# Gumstix_Overo.net
KiCad netlist of a schematic drawn in Altium Designer
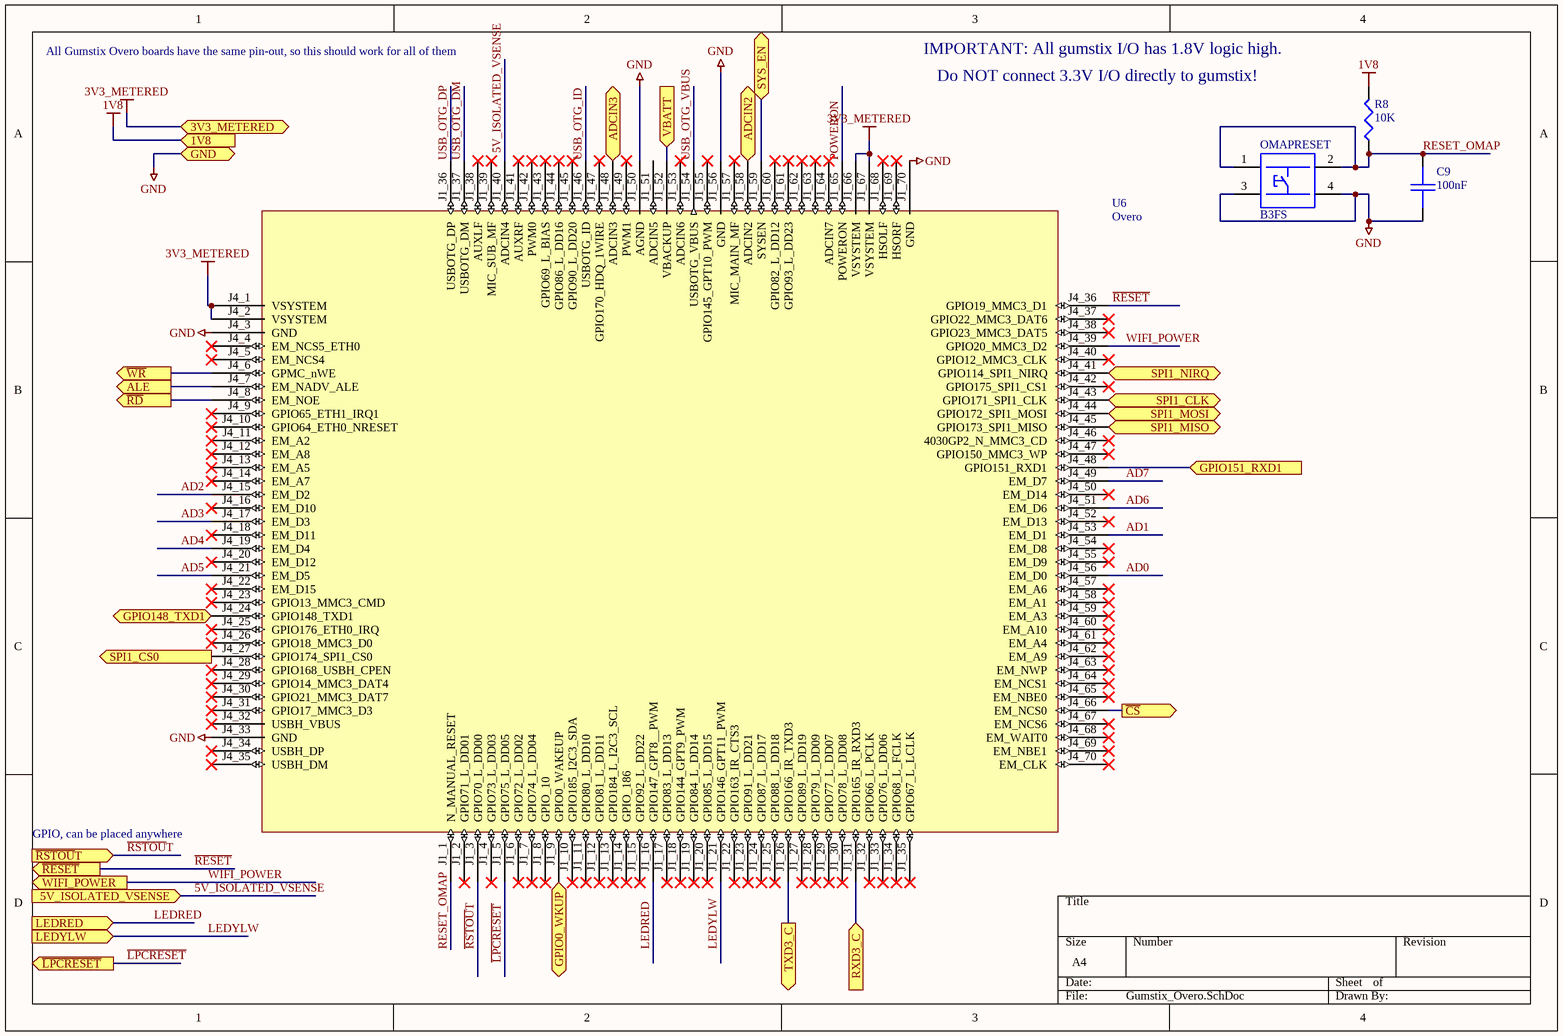
[diagram p0: Gumstix_Overo.SchDoc]

(export (version "E")
  (design (tool "Eeschema 10.0.6"))
  (components
    (comp (ref "C9")
      (value "100nF")
      (footprint "0603")
      (description "Capacitor")
      (libsource (lib "RCLDQ") (part "CAP"))
    )
    (comp (ref "OMAPRESET")
      (value "B3FS")
      (footprint "B3FS-1052")
      (description "SMD tactile switch")
      (libsource (lib "Miscellaneous") (part "B3FS"))
    )
    (comp (ref "R8")
      (value "10K")
      (footprint "0603")
      (description "Resistor")
      (libsource (lib "RCLDQ") (part "RES1"))
    )
    (comp (ref "U6")
      (value "Overo")
      (footprint "Overo-bare")
      (description "Gumstix Overo Motherboard")
      (libsource (lib "gumstix") (part "Overo"))
    )
  )
  (nets
    (net (code "1") (name "/5V_ISOLATED_VSENSE") (class "Default")
      (node (ref "U6") (pin "J1_40") (pinfunction "ADCIN4_J1_40") (pintype "bidirectional"))
    )
    (net (code "2") (name "/AD0") (class "Default")
      (node (ref "U6") (pin "J4_56") (pinfunction "EM_D0_J4_56") (pintype "bidirectional"))
    )
    (net (code "3") (name "/AD1") (class "Default")
      (node (ref "U6") (pin "J4_53") (pinfunction "EM_D1_J4_53") (pintype "bidirectional"))
    )
    (net (code "4") (name "/AD2") (class "Default")
      (node (ref "U6") (pin "J4_15") (pinfunction "EM_D2_J4_15") (pintype "bidirectional"))
    )
    (net (code "5") (name "/AD3") (class "Default")
      (node (ref "U6") (pin "J4_17") (pinfunction "EM_D3_J4_17") (pintype "bidirectional"))
    )
    (net (code "6") (name "/AD4") (class "Default")
      (node (ref "U6") (pin "J4_19") (pinfunction "EM_D4_J4_19") (pintype "bidirectional"))
    )
    (net (code "7") (name "/AD5") (class "Default")
      (node (ref "U6") (pin "J4_21") (pinfunction "EM_D5_J4_21") (pintype "bidirectional"))
    )
    (net (code "8") (name "/AD6") (class "Default")
      (node (ref "U6") (pin "J4_51") (pinfunction "EM_D6_J4_51") (pintype "bidirectional"))
    )
    (net (code "9") (name "/AD7") (class "Default")
      (node (ref "U6") (pin "J4_49") (pinfunction "EM_D7_J4_49") (pintype "bidirectional"))
    )
    (net (code "10") (name "/ADCIN2") (class "Default")
      (node (ref "U6") (pin "J1_58") (pinfunction "ADCIN2_J1_58") (pintype "bidirectional"))
    )
    (net (code "11") (name "/ADCIN3") (class "Default")
      (node (ref "U6") (pin "J1_48") (pinfunction "ADCIN3_J1_48") (pintype "bidirectional"))
    )
    (net (code "12") (name "/ALE") (class "Default")
      (node (ref "U6") (pin "J4_7") (pinfunction "EM_NADV_ALE_J4_7") (pintype "bidirectional"))
    )
    (net (code "13") (name "/GPIO0_WKUP") (class "Default")
      (node (ref "U6") (pin "J1_9") (pinfunction "GPIO0_WAKEUP_J1_9") (pintype "bidirectional"))
    )
    (net (code "14") (name "/GPIO148_TXD1") (class "Default")
      (node (ref "U6") (pin "J4_24") (pinfunction "GPIO148_TXD1_J4_24") (pintype "bidirectional"))
    )
    (net (code "15") (name "/GPIO151_RXD1") (class "Default")
      (node (ref "U6") (pin "J4_48") (pinfunction "GPIO151_RXD1_J4_48") (pintype "bidirectional"))
    )
    (net (code "16") (name "/LEDRED") (class "Default")
      (node (ref "U6") (pin "J1_16") (pinfunction "GPIO147_GPT8__PWM_J1_16") (pintype "bidirectional"))
    )
    (net (code "17") (name "/LEDYLW") (class "Default")
      (node (ref "U6") (pin "J1_21") (pinfunction "GPIO146_GPT11_PWM_J1_21") (pintype "bidirectional"))
    )
    (net (code "18") (name "/POWERON") (class "Default")
      (node (ref "U6") (pin "J1_65") (pinfunction "POWERON_J1_65") (pintype "bidirectional"))
    )
    (net (code "19") (name "/RESET_OMAP") (class "Default")
      (node (ref "C9") (pin "1") (pinfunction "1_1") (pintype "passive"))
      (node (ref "OMAPRESET") (pin "1") (pinfunction "A1_1") (pintype "passive"))
      (node (ref "OMAPRESET") (pin "2") (pinfunction "A2_2") (pintype "passive"))
      (node (ref "R8") (pin "1") (pinfunction "1_1") (pintype "passive"))
      (node (ref "U6") (pin "J1_1") (pinfunction "N_MANUAL_RESET_J1_1") (pintype "bidirectional"))
    )
    (net (code "20") (name "/RXD3_C") (class "Default")
      (node (ref "U6") (pin "J1_31") (pinfunction "GPIO165_IR_RXD3_J1_31") (pintype "bidirectional"))
    )
    (net (code "21") (name "/SPI1_CLK") (class "Default")
      (node (ref "U6") (pin "J4_43") (pinfunction "GPIO171_SPI1_CLK_J4_43") (pintype "bidirectional"))
    )
    (net (code "22") (name "/SPI1_CS0") (class "Default")
      (node (ref "U6") (pin "J4_27") (pinfunction "GPIO174_SPI1_CS0_J4_27") (pintype "bidirectional"))
    )
    (net (code "23") (name "/SPI1_MISO") (class "Default")
      (node (ref "U6") (pin "J4_45") (pinfunction "GPIO173_SPI1_MISO_J4_45") (pintype "bidirectional"))
    )
    (net (code "24") (name "/SPI1_MOSI") (class "Default")
      (node (ref "U6") (pin "J4_44") (pinfunction "GPIO172_SPI1_MOSI_J4_44") (pintype "bidirectional"))
    )
    (net (code "25") (name "/SPI1_NIRQ") (class "Default")
      (node (ref "U6") (pin "J4_41") (pinfunction "GPIO114_SPI1_NIRQ_J4_41") (pintype "bidirectional"))
    )
    (net (code "26") (name "/SYS_EN") (class "Default")
      (node (ref "U6") (pin "J1_59") (pinfunction "SYSEN_J1_59") (pintype "bidirectional"))
    )
    (net (code "27") (name "/TXD3_C") (class "Default")
      (node (ref "U6") (pin "J1_26") (pinfunction "GPIO166_IR_TXD3_J1_26") (pintype "bidirectional"))
    )
    (net (code "28") (name "/USB_OTG_DM") (class "Default")
      (node (ref "U6") (pin "J1_37") (pinfunction "USBOTG_DM_J1_37") (pintype "bidirectional"))
    )
    (net (code "29") (name "/USB_OTG_DP") (class "Default")
      (node (ref "U6") (pin "J1_36") (pinfunction "USBOTG_DP_J1_36") (pintype "bidirectional"))
    )
    (net (code "30") (name "/USB_OTG_ID") (class "Default")
      (node (ref "U6") (pin "J1_46") (pinfunction "USBOTG_ID_J1_46") (pintype "bidirectional"))
    )
    (net (code "31") (name "/USB_OTG_VBUS") (class "Default")
      (node (ref "U6") (pin "J1_54") (pinfunction "USBOTG_VBUS_J1_54") (pintype "output"))
    )
    (net (code "32") (name "/VBATT") (class "Default")
      (node (ref "U6") (pin "J1_52") (pinfunction "VBACKUP_J1_52") (pintype "power_in"))
    )
    (net (code "33") (name "/WIFI_POWER") (class "Default")
      (node (ref "U6") (pin "J4_39") (pinfunction "GPIO20_MMC3_D2_J4_39") (pintype "bidirectional"))
    )
    (net (code "34") (name "/~{CS}") (class "Default")
      (node (ref "U6") (pin "J4_66") (pinfunction "EM_NCS0_J4_66") (pintype "bidirectional"))
    )
    (net (code "35") (name "/~{LPCRESET}") (class "Default")
      (node (ref "U6") (pin "J1_5") (pinfunction "GPIO75_L_DD05_J1_5") (pintype "bidirectional"))
    )
    (net (code "36") (name "/~{RD}") (class "Default")
      (node (ref "U6") (pin "J4_8") (pinfunction "EM_NOE_J4_8") (pintype "bidirectional"))
    )
    (net (code "37") (name "/~{RESET}") (class "Default")
      (node (ref "U6") (pin "J4_36") (pinfunction "GPIO19_MMC3_D1_J4_36") (pintype "bidirectional"))
    )
    (net (code "38") (name "/~{RSTOU}T") (class "Default")
      (node (ref "U6") (pin "J1_3") (pinfunction "GPIO70_L_DD00_J1_3") (pintype "bidirectional"))
    )
    (net (code "39") (name "/~{WR}") (class "Default")
      (node (ref "U6") (pin "J4_6") (pinfunction "GPMC_nWE_J4_6") (pintype "bidirectional"))
    )
    (net (code "40") (name "1V8") (class "Default")
      (node (ref "R8") (pin "2") (pinfunction "2_2") (pintype "passive"))
    )
    (net (code "41") (name "3V3_METERED") (class "Default")
      (node (ref "U6") (pin "J1_66") (pinfunction "VSYSTEM_J1_66") (pintype "power_in"))
      (node (ref "U6") (pin "J1_67") (pinfunction "VSYSTEM_J1_67") (pintype "power_in"))
      (node (ref "U6") (pin "J4_1") (pinfunction "VSYSTEM_J4_1") (pintype "power_in"))
      (node (ref "U6") (pin "J4_2") (pinfunction "VSYSTEM_J4_2") (pintype "power_in"))
    )
    (net (code "42") (name "GND") (class "Default")
      (node (ref "C9") (pin "2") (pinfunction "2_2") (pintype "passive"))
      (node (ref "OMAPRESET") (pin "3") (pinfunction "B2_3") (pintype "passive"))
      (node (ref "OMAPRESET") (pin "4") (pinfunction "B1_4") (pintype "passive"))
      (node (ref "U6") (pin "J1_50") (pinfunction "AGND_J1_50") (pintype "power_in"))
      (node (ref "U6") (pin "J1_56") (pinfunction "GND_J1_56") (pintype "power_in"))
      (node (ref "U6") (pin "J1_70") (pinfunction "GND_J1_70") (pintype "power_in"))
      (node (ref "U6") (pin "J4_3") (pinfunction "GND_J4_3") (pintype "power_in"))
      (node (ref "U6") (pin "J4_33") (pinfunction "GND_J4_33") (pintype "power_in"))
    )
    (net (code "43") (name "unconnected-(U6-4030GP2_N_MMC3_CD-PadJ4_46)") (class "Default")
      (node (ref "U6") (pin "J4_46") (pinfunction "4030GP2_N_MMC3_CD_J4_46") (pintype "bidirectional+no_connect"))
    )
    (net (code "44") (name "unconnected-(U6-ADCIN5-PadJ1_51)") (class "Default")
      (node (ref "U6") (pin "J1_51") (pinfunction "ADCIN5_J1_51") (pintype "bidirectional"))
    )
    (net (code "45") (name "unconnected-(U6-ADCIN6-PadJ1_53)") (class "Default")
      (node (ref "U6") (pin "J1_53") (pinfunction "ADCIN6_J1_53") (pintype "bidirectional+no_connect"))
    )
    (net (code "46") (name "unconnected-(U6-ADCIN7-PadJ1_64)") (class "Default")
      (node (ref "U6") (pin "J1_64") (pinfunction "ADCIN7_J1_64") (pintype "bidirectional+no_connect"))
    )
    (net (code "47") (name "unconnected-(U6-AUXLF-PadJ1_38)") (class "Default")
      (node (ref "U6") (pin "J1_38") (pinfunction "AUXLF_J1_38") (pintype "bidirectional+no_connect"))
    )
    (net (code "48") (name "unconnected-(U6-AUXRF-PadJ1_41)") (class "Default")
      (node (ref "U6") (pin "J1_41") (pinfunction "AUXRF_J1_41") (pintype "bidirectional+no_connect"))
    )
    (net (code "49") (name "unconnected-(U6-EM_A1-PadJ4_58)") (class "Default")
      (node (ref "U6") (pin "J4_58") (pinfunction "EM_A1_J4_58") (pintype "bidirectional+no_connect"))
    )
    (net (code "50") (name "unconnected-(U6-EM_A2-PadJ4_11)") (class "Default")
      (node (ref "U6") (pin "J4_11") (pinfunction "EM_A2_J4_11") (pintype "bidirectional+no_connect"))
    )
    (net (code "51") (name "unconnected-(U6-EM_A3-PadJ4_59)") (class "Default")
      (node (ref "U6") (pin "J4_59") (pinfunction "EM_A3_J4_59") (pintype "bidirectional+no_connect"))
    )
    (net (code "52") (name "unconnected-(U6-EM_A4-PadJ4_61)") (class "Default")
      (node (ref "U6") (pin "J4_61") (pinfunction "EM_A4_J4_61") (pintype "bidirectional+no_connect"))
    )
    (net (code "53") (name "unconnected-(U6-EM_A5-PadJ4_13)") (class "Default")
      (node (ref "U6") (pin "J4_13") (pinfunction "EM_A5_J4_13") (pintype "bidirectional+no_connect"))
    )
    (net (code "54") (name "unconnected-(U6-EM_A6-PadJ4_57)") (class "Default")
      (node (ref "U6") (pin "J4_57") (pinfunction "EM_A6_J4_57") (pintype "bidirectional+no_connect"))
    )
    (net (code "55") (name "unconnected-(U6-EM_A7-PadJ4_14)") (class "Default")
      (node (ref "U6") (pin "J4_14") (pinfunction "EM_A7_J4_14") (pintype "bidirectional+no_connect"))
    )
    (net (code "56") (name "unconnected-(U6-EM_A8-PadJ4_12)") (class "Default")
      (node (ref "U6") (pin "J4_12") (pinfunction "EM_A8_J4_12") (pintype "bidirectional+no_connect"))
    )
    (net (code "57") (name "unconnected-(U6-EM_A9-PadJ4_62)") (class "Default")
      (node (ref "U6") (pin "J4_62") (pinfunction "EM_A9_J4_62") (pintype "bidirectional+no_connect"))
    )
    (net (code "58") (name "unconnected-(U6-EM_A10-PadJ4_60)") (class "Default")
      (node (ref "U6") (pin "J4_60") (pinfunction "EM_A10_J4_60") (pintype "bidirectional+no_connect"))
    )
    (net (code "59") (name "unconnected-(U6-EM_CLK-PadJ4_70)") (class "Default")
      (node (ref "U6") (pin "J4_70") (pinfunction "EM_CLK_J4_70") (pintype "bidirectional+no_connect"))
    )
    (net (code "60") (name "unconnected-(U6-EM_D8-PadJ4_54)") (class "Default")
      (node (ref "U6") (pin "J4_54") (pinfunction "EM_D8_J4_54") (pintype "bidirectional+no_connect"))
    )
    (net (code "61") (name "unconnected-(U6-EM_D9-PadJ4_55)") (class "Default")
      (node (ref "U6") (pin "J4_55") (pinfunction "EM_D9_J4_55") (pintype "bidirectional+no_connect"))
    )
    (net (code "62") (name "unconnected-(U6-EM_D10-PadJ4_16)") (class "Default")
      (node (ref "U6") (pin "J4_16") (pinfunction "EM_D10_J4_16") (pintype "bidirectional+no_connect"))
    )
    (net (code "63") (name "unconnected-(U6-EM_D11-PadJ4_18)") (class "Default")
      (node (ref "U6") (pin "J4_18") (pinfunction "EM_D11_J4_18") (pintype "bidirectional+no_connect"))
    )
    (net (code "64") (name "unconnected-(U6-EM_D12-PadJ4_20)") (class "Default")
      (node (ref "U6") (pin "J4_20") (pinfunction "EM_D12_J4_20") (pintype "bidirectional+no_connect"))
    )
    (net (code "65") (name "unconnected-(U6-EM_D13-PadJ4_52)") (class "Default")
      (node (ref "U6") (pin "J4_52") (pinfunction "EM_D13_J4_52") (pintype "bidirectional+no_connect"))
    )
    (net (code "66") (name "unconnected-(U6-EM_D14-PadJ4_50)") (class "Default")
      (node (ref "U6") (pin "J4_50") (pinfunction "EM_D14_J4_50") (pintype "bidirectional+no_connect"))
    )
    (net (code "67") (name "unconnected-(U6-EM_D15-PadJ4_22)") (class "Default")
      (node (ref "U6") (pin "J4_22") (pinfunction "EM_D15_J4_22") (pintype "bidirectional+no_connect"))
    )
    (net (code "68") (name "unconnected-(U6-EM_NBE0-PadJ4_65)") (class "Default")
      (node (ref "U6") (pin "J4_65") (pinfunction "EM_NBE0_J4_65") (pintype "bidirectional+no_connect"))
    )
    (net (code "69") (name "unconnected-(U6-EM_NBE1-PadJ4_69)") (class "Default")
      (node (ref "U6") (pin "J4_69") (pinfunction "EM_NBE1_J4_69") (pintype "bidirectional+no_connect"))
    )
    (net (code "70") (name "unconnected-(U6-EM_NCS1-PadJ4_64)") (class "Default")
      (node (ref "U6") (pin "J4_64") (pinfunction "EM_NCS1_J4_64") (pintype "bidirectional+no_connect"))
    )
    (net (code "71") (name "unconnected-(U6-EM_NCS4-PadJ4_5)") (class "Default")
      (node (ref "U6") (pin "J4_5") (pinfunction "EM_NCS4_J4_5") (pintype "bidirectional+no_connect"))
    )
    (net (code "72") (name "unconnected-(U6-EM_NCS5_ETH0-PadJ4_4)") (class "Default")
      (node (ref "U6") (pin "J4_4") (pinfunction "EM_NCS5_ETH0_J4_4") (pintype "bidirectional+no_connect"))
    )
    (net (code "73") (name "unconnected-(U6-EM_NCS6-PadJ4_67)") (class "Default")
      (node (ref "U6") (pin "J4_67") (pinfunction "EM_NCS6_J4_67") (pintype "bidirectional+no_connect"))
    )
    (net (code "74") (name "unconnected-(U6-EM_NWP-PadJ4_63)") (class "Default")
      (node (ref "U6") (pin "J4_63") (pinfunction "EM_NWP_J4_63") (pintype "bidirectional+no_connect"))
    )
    (net (code "75") (name "unconnected-(U6-EM_WAIT0-PadJ4_68)") (class "Default")
      (node (ref "U6") (pin "J4_68") (pinfunction "EM_WAIT0_J4_68") (pintype "bidirectional+no_connect"))
    )
    (net (code "76") (name "unconnected-(U6-GPIO12_MMC3_CLK-PadJ4_40)") (class "Default")
      (node (ref "U6") (pin "J4_40") (pinfunction "GPIO12_MMC3_CLK_J4_40") (pintype "bidirectional+no_connect"))
    )
    (net (code "77") (name "unconnected-(U6-GPIO13_MMC3_CMD-PadJ4_23)") (class "Default")
      (node (ref "U6") (pin "J4_23") (pinfunction "GPIO13_MMC3_CMD_J4_23") (pintype "bidirectional+no_connect"))
    )
    (net (code "78") (name "unconnected-(U6-GPIO14_MMC3_DAT4-PadJ4_29)") (class "Default")
      (node (ref "U6") (pin "J4_29") (pinfunction "GPIO14_MMC3_DAT4_J4_29") (pintype "bidirectional+no_connect"))
    )
    (net (code "79") (name "unconnected-(U6-GPIO17_MMC3_D3-PadJ4_31)") (class "Default")
      (node (ref "U6") (pin "J4_31") (pinfunction "GPIO17_MMC3_D3_J4_31") (pintype "bidirectional+no_connect"))
    )
    (net (code "80") (name "unconnected-(U6-GPIO18_MMC3_D0-PadJ4_26)") (class "Default")
      (node (ref "U6") (pin "J4_26") (pinfunction "GPIO18_MMC3_D0_J4_26") (pintype "bidirectional+no_connect"))
    )
    (net (code "81") (name "unconnected-(U6-GPIO21_MMC3_DAT7-PadJ4_30)") (class "Default")
      (node (ref "U6") (pin "J4_30") (pinfunction "GPIO21_MMC3_DAT7_J4_30") (pintype "bidirectional+no_connect"))
    )
    (net (code "82") (name "unconnected-(U6-GPIO22_MMC3_DAT6-PadJ4_37)") (class "Default")
      (node (ref "U6") (pin "J4_37") (pinfunction "GPIO22_MMC3_DAT6_J4_37") (pintype "bidirectional+no_connect"))
    )
    (net (code "83") (name "unconnected-(U6-GPIO23_MMC3_DAT5-PadJ4_38)") (class "Default")
      (node (ref "U6") (pin "J4_38") (pinfunction "GPIO23_MMC3_DAT5_J4_38") (pintype "bidirectional+no_connect"))
    )
    (net (code "84") (name "unconnected-(U6-GPIO64_ETH0_NRESET-PadJ4_10)") (class "Default")
      (node (ref "U6") (pin "J4_10") (pinfunction "GPIO64_ETH0_NRESET_J4_10") (pintype "bidirectional+no_connect"))
    )
    (net (code "85") (name "unconnected-(U6-GPIO65_ETH1_IRQ1-PadJ4_9)") (class "Default")
      (node (ref "U6") (pin "J4_9") (pinfunction "GPIO65_ETH1_IRQ1_J4_9") (pintype "bidirectional+no_connect"))
    )
    (net (code "86") (name "unconnected-(U6-GPIO66_L_PCLK-PadJ1_32)") (class "Default")
      (node (ref "U6") (pin "J1_32") (pinfunction "GPIO66_L_PCLK_J1_32") (pintype "bidirectional+no_connect"))
    )
    (net (code "87") (name "unconnected-(U6-GPIO67_L_LCLK-PadJ1_35)") (class "Default")
      (node (ref "U6") (pin "J1_35") (pinfunction "GPIO67_L_LCLK_J1_35") (pintype "bidirectional+no_connect"))
    )
    (net (code "88") (name "unconnected-(U6-GPIO68_L_FCLK-PadJ1_34)") (class "Default")
      (node (ref "U6") (pin "J1_34") (pinfunction "GPIO68_L_FCLK_J1_34") (pintype "bidirectional+no_connect"))
    )
    (net (code "89") (name "unconnected-(U6-GPIO69_L_BIAS-PadJ1_43)") (class "Default")
      (node (ref "U6") (pin "J1_43") (pinfunction "GPIO69_L_BIAS_J1_43") (pintype "bidirectional+no_connect"))
    )
    (net (code "90") (name "unconnected-(U6-GPIO71_L_DD01-PadJ1_2)") (class "Default")
      (node (ref "U6") (pin "J1_2") (pinfunction "GPIO71_L_DD01_J1_2") (pintype "bidirectional+no_connect"))
    )
    (net (code "91") (name "unconnected-(U6-GPIO72_L_DD02-PadJ1_6)") (class "Default")
      (node (ref "U6") (pin "J1_6") (pinfunction "GPIO72_L_DD02_J1_6") (pintype "bidirectional+no_connect"))
    )
    (net (code "92") (name "unconnected-(U6-GPIO73_L_DD03-PadJ1_4)") (class "Default")
      (node (ref "U6") (pin "J1_4") (pinfunction "GPIO73_L_DD03_J1_4") (pintype "bidirectional+no_connect"))
    )
    (net (code "93") (name "unconnected-(U6-GPIO74_L_DD04-PadJ1_7)") (class "Default")
      (node (ref "U6") (pin "J1_7") (pinfunction "GPIO74_L_DD04_J1_7") (pintype "bidirectional+no_connect"))
    )
    (net (code "94") (name "unconnected-(U6-GPIO76_L_DD06-PadJ1_33)") (class "Default")
      (node (ref "U6") (pin "J1_33") (pinfunction "GPIO76_L_DD06_J1_33") (pintype "bidirectional+no_connect"))
    )
    (net (code "95") (name "unconnected-(U6-GPIO77_L_DD07-PadJ1_29)") (class "Default")
      (node (ref "U6") (pin "J1_29") (pinfunction "GPIO77_L_DD07_J1_29") (pintype "bidirectional+no_connect"))
    )
    (net (code "96") (name "unconnected-(U6-GPIO78_L_DD08-PadJ1_30)") (class "Default")
      (node (ref "U6") (pin "J1_30") (pinfunction "GPIO78_L_DD08_J1_30") (pintype "bidirectional+no_connect"))
    )
    (net (code "97") (name "unconnected-(U6-GPIO79_L_DD09-PadJ1_28)") (class "Default")
      (node (ref "U6") (pin "J1_28") (pinfunction "GPIO79_L_DD09_J1_28") (pintype "bidirectional+no_connect"))
    )
    (net (code "98") (name "unconnected-(U6-GPIO80_L_DD10-PadJ1_11)") (class "Default")
      (node (ref "U6") (pin "J1_11") (pinfunction "GPIO80_L_DD10_J1_11") (pintype "bidirectional+no_connect"))
    )
    (net (code "99") (name "unconnected-(U6-GPIO81_L_DD11-PadJ1_12)") (class "Default")
      (node (ref "U6") (pin "J1_12") (pinfunction "GPIO81_L_DD11_J1_12") (pintype "bidirectional+no_connect"))
    )
    (net (code "100") (name "unconnected-(U6-GPIO82_L_DD12-PadJ1_60)") (class "Default")
      (node (ref "U6") (pin "J1_60") (pinfunction "GPIO82_L_DD12_J1_60") (pintype "bidirectional+no_connect"))
    )
    (net (code "101") (name "unconnected-(U6-GPIO83_L_DD13-PadJ1_17)") (class "Default")
      (node (ref "U6") (pin "J1_17") (pinfunction "GPIO83_L_DD13_J1_17") (pintype "bidirectional+no_connect"))
    )
    (net (code "102") (name "unconnected-(U6-GPIO84_L_DD14-PadJ1_19)") (class "Default")
      (node (ref "U6") (pin "J1_19") (pinfunction "GPIO84_L_DD14_J1_19") (pintype "bidirectional+no_connect"))
    )
    (net (code "103") (name "unconnected-(U6-GPIO85_L_DD15-PadJ1_20)") (class "Default")
      (node (ref "U6") (pin "J1_20") (pinfunction "GPIO85_L_DD15_J1_20") (pintype "bidirectional+no_connect"))
    )
    (net (code "104") (name "unconnected-(U6-GPIO86_L_DD16-PadJ1_44)") (class "Default")
      (node (ref "U6") (pin "J1_44") (pinfunction "GPIO86_L_DD16_J1_44") (pintype "bidirectional+no_connect"))
    )
    (net (code "105") (name "unconnected-(U6-GPIO87_L_DD17-PadJ1_24)") (class "Default")
      (node (ref "U6") (pin "J1_24") (pinfunction "GPIO87_L_DD17_J1_24") (pintype "bidirectional+no_connect"))
    )
    (net (code "106") (name "unconnected-(U6-GPIO88_L_DD18-PadJ1_25)") (class "Default")
      (node (ref "U6") (pin "J1_25") (pinfunction "GPIO88_L_DD18_J1_25") (pintype "bidirectional+no_connect"))
    )
    (net (code "107") (name "unconnected-(U6-GPIO89_L_DD19-PadJ1_27)") (class "Default")
      (node (ref "U6") (pin "J1_27") (pinfunction "GPIO89_L_DD19_J1_27") (pintype "bidirectional+no_connect"))
    )
    (net (code "108") (name "unconnected-(U6-GPIO90_L_DD20-PadJ1_45)") (class "Default")
      (node (ref "U6") (pin "J1_45") (pinfunction "GPIO90_L_DD20_J1_45") (pintype "bidirectional+no_connect"))
    )
    (net (code "109") (name "unconnected-(U6-GPIO91_L_DD21-PadJ1_23)") (class "Default")
      (node (ref "U6") (pin "J1_23") (pinfunction "GPIO91_L_DD21_J1_23") (pintype "bidirectional+no_connect"))
    )
    (net (code "110") (name "unconnected-(U6-GPIO92_L_DD22-PadJ1_15)") (class "Default")
      (node (ref "U6") (pin "J1_15") (pinfunction "GPIO92_L_DD22_J1_15") (pintype "bidirectional+no_connect"))
    )
    (net (code "111") (name "unconnected-(U6-GPIO93_L_DD23-PadJ1_61)") (class "Default")
      (node (ref "U6") (pin "J1_61") (pinfunction "GPIO93_L_DD23_J1_61") (pintype "bidirectional+no_connect"))
    )
    (net (code "112") (name "unconnected-(U6-GPIO144_GPT9_PWM-PadJ1_18)") (class "Default")
      (node (ref "U6") (pin "J1_18") (pinfunction "GPIO144_GPT9_PWM_J1_18") (pintype "bidirectional+no_connect"))
    )
    (net (code "113") (name "unconnected-(U6-GPIO145_GPT10_PWM-PadJ1_55)") (class "Default")
      (node (ref "U6") (pin "J1_55") (pinfunction "GPIO145_GPT10_PWM_J1_55") (pintype "bidirectional+no_connect"))
    )
    (net (code "114") (name "unconnected-(U6-GPIO150_MMC3_WP-PadJ4_47)") (class "Default")
      (node (ref "U6") (pin "J4_47") (pinfunction "GPIO150_MMC3_WP_J4_47") (pintype "bidirectional+no_connect"))
    )
    (net (code "115") (name "unconnected-(U6-GPIO163_IR_CTS3-PadJ1_22)") (class "Default")
      (node (ref "U6") (pin "J1_22") (pinfunction "GPIO163_IR_CTS3_J1_22") (pintype "bidirectional+no_connect"))
    )
    (net (code "116") (name "unconnected-(U6-GPIO168_USBH_CPEN-PadJ4_28)") (class "Default")
      (node (ref "U6") (pin "J4_28") (pinfunction "GPIO168_USBH_CPEN_J4_28") (pintype "bidirectional+no_connect"))
    )
    (net (code "117") (name "unconnected-(U6-GPIO170_HDQ_1WIRE-PadJ1_47)") (class "Default")
      (node (ref "U6") (pin "J1_47") (pinfunction "GPIO170_HDQ_1WIRE_J1_47") (pintype "bidirectional+no_connect"))
    )
    (net (code "118") (name "unconnected-(U6-GPIO175_SPI1_CS1-PadJ4_42)") (class "Default")
      (node (ref "U6") (pin "J4_42") (pinfunction "GPIO175_SPI1_CS1_J4_42") (pintype "bidirectional+no_connect"))
    )
    (net (code "119") (name "unconnected-(U6-GPIO176_ETH0_IRQ-PadJ4_25)") (class "Default")
      (node (ref "U6") (pin "J4_25") (pinfunction "GPIO176_ETH0_IRQ_J4_25") (pintype "bidirectional+no_connect"))
    )
    (net (code "120") (name "unconnected-(U6-GPIO184_L_I2C3_SCL-PadJ1_13)") (class "Default")
      (node (ref "U6") (pin "J1_13") (pinfunction "GPIO184_L_I2C3_SCL_J1_13") (pintype "bidirectional+no_connect"))
    )
    (net (code "121") (name "unconnected-(U6-GPIO185_I2C3_SDA-PadJ1_10)") (class "Default")
      (node (ref "U6") (pin "J1_10") (pinfunction "GPIO185_I2C3_SDA_J1_10") (pintype "bidirectional+no_connect"))
    )
    (net (code "122") (name "unconnected-(U6-GPIO_10-PadJ1_8)") (class "Default")
      (node (ref "U6") (pin "J1_8") (pinfunction "GPIO_10_J1_8") (pintype "bidirectional+no_connect"))
    )
    (net (code "123") (name "unconnected-(U6-GPIO_186-PadJ1_14)") (class "Default")
      (node (ref "U6") (pin "J1_14") (pinfunction "GPIO_186_J1_14") (pintype "bidirectional+no_connect"))
    )
    (net (code "124") (name "unconnected-(U6-HSOLF-PadJ1_68)") (class "Default")
      (node (ref "U6") (pin "J1_68") (pinfunction "HSOLF_J1_68") (pintype "bidirectional+no_connect"))
    )
    (net (code "125") (name "unconnected-(U6-HSORF-PadJ1_69)") (class "Default")
      (node (ref "U6") (pin "J1_69") (pinfunction "HSORF_J1_69") (pintype "bidirectional+no_connect"))
    )
    (net (code "126") (name "unconnected-(U6-MIC_MAIN_MF-PadJ1_57)") (class "Default")
      (node (ref "U6") (pin "J1_57") (pinfunction "MIC_MAIN_MF_J1_57") (pintype "bidirectional+no_connect"))
    )
    (net (code "127") (name "unconnected-(U6-MIC_SUB_MF-PadJ1_39)") (class "Default")
      (node (ref "U6") (pin "J1_39") (pinfunction "MIC_SUB_MF_J1_39") (pintype "bidirectional+no_connect"))
    )
    (net (code "128") (name "unconnected-(U6-PWM0-PadJ1_42)") (class "Default")
      (node (ref "U6") (pin "J1_42") (pinfunction "PWM0_J1_42") (pintype "bidirectional+no_connect"))
    )
    (net (code "129") (name "unconnected-(U6-PWM1-PadJ1_49)") (class "Default")
      (node (ref "U6") (pin "J1_49") (pinfunction "PWM1_J1_49") (pintype "bidirectional+no_connect"))
    )
    (net (code "130") (name "unconnected-(U6-PadJ1_62)") (class "Default")
      (node (ref "U6") (pin "J1_62") (pintype "bidirectional+no_connect"))
    )
    (net (code "131") (name "unconnected-(U6-PadJ1_63)") (class "Default")
      (node (ref "U6") (pin "J1_63") (pintype "bidirectional+no_connect"))
    )
    (net (code "132") (name "unconnected-(U6-USBH_DM-PadJ4_35)") (class "Default")
      (node (ref "U6") (pin "J4_35") (pinfunction "USBH_DM_J4_35") (pintype "bidirectional+no_connect"))
    )
    (net (code "133") (name "unconnected-(U6-USBH_DP-PadJ4_34)") (class "Default")
      (node (ref "U6") (pin "J4_34") (pinfunction "USBH_DP_J4_34") (pintype "bidirectional+no_connect"))
    )
    (net (code "134") (name "unconnected-(U6-USBH_VBUS-PadJ4_32)") (class "Default")
      (node (ref "U6") (pin "J4_32") (pinfunction "USBH_VBUS_J4_32") (pintype "power_in+no_connect"))
    )
  )
)
